# lt3042.net
KiCad netlist of a schematic drawn in EAGLE
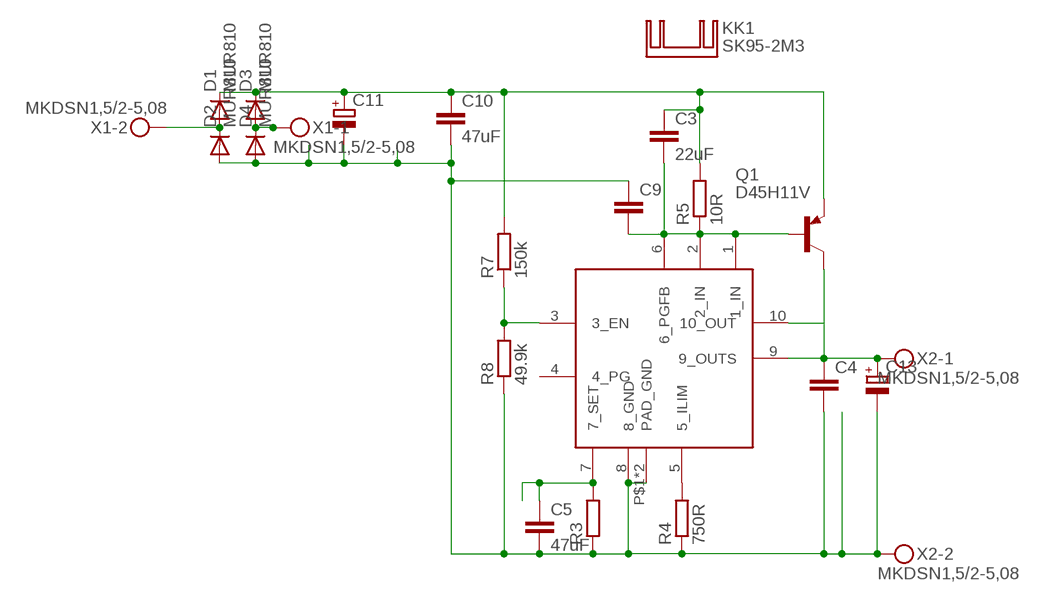
[diagram p0: schematic, sheet 1]

(export (version "E")
  (design (tool "Eeschema 10.0.6"))
  (components
    (comp (ref "C3")
      (value "22uF")
      (footprint "eagle-import:C1210")
      (libsource (lib "eagle-import") (part "C-EUC1210"))
    )
    (comp (ref "C4")
      (value "C-EUC1206")
      (footprint "eagle-import:C1206")
      (libsource (lib "eagle-import") (part "C-EUC1206"))
    )
    (comp (ref "C5")
      (value "47uF")
      (footprint "eagle-import:C1210")
      (libsource (lib "eagle-import") (part "C-EUC1210"))
    )
    (comp (ref "C9")
      (value "C-EUC1206")
      (footprint "eagle-import:C1206")
      (libsource (lib "eagle-import") (part "C-EUC1206"))
    )
    (comp (ref "C10")
      (value "47uF")
      (footprint "eagle-import:C1210")
      (libsource (lib "eagle-import") (part "C-EUC1210"))
    )
    (comp (ref "C11")
      (value "CPOL-EUE7.5-18")
      (footprint "eagle-import:E7,5-18")
      (libsource (lib "eagle-import") (part "CPOL-EUE7.5-18"))
    )
    (comp (ref "C13")
      (value "CPOL-EUE5-10.5")
      (footprint "eagle-import:E5-10,5")
      (libsource (lib "eagle-import") (part "CPOL-EUE5-10.5"))
    )
    (comp (ref "D1")
      (value "MUR810")
      (footprint "eagle-import:TO220ACS")
      (libsource (lib "eagle-import") (part "MUR810"))
    )
    (comp (ref "D2")
      (value "MUR810")
      (footprint "eagle-import:TO220ACS")
      (libsource (lib "eagle-import") (part "MUR810"))
    )
    (comp (ref "D3")
      (value "MUR810")
      (footprint "eagle-import:TO220ACS")
      (libsource (lib "eagle-import") (part "MUR810"))
    )
    (comp (ref "D4")
      (value "MUR810")
      (footprint "eagle-import:TO220ACS")
      (libsource (lib "eagle-import") (part "MUR810"))
    )
    (comp (ref "KK1")
      (value "SK95-2M3")
      (footprint "eagle-import:SK95-2M3")
      (libsource (lib "eagle-import") (part "SK95-2M3"))
    )
    (comp (ref "Q1")
      (value "D45H11V")
      (footprint "eagle-import:TO220V")
      (libsource (lib "eagle-import") (part "D45H11V"))
    )
    (comp (ref "R3")
      (value "R-EU_R1206")
      (footprint "eagle-import:R1206")
      (libsource (lib "eagle-import") (part "R-EU_R1206"))
    )
    (comp (ref "R4")
      (value "750R")
      (footprint "eagle-import:R1206")
      (libsource (lib "eagle-import") (part "R-EU_R1206"))
    )
    (comp (ref "R5")
      (value "10R")
      (footprint "eagle-import:R1206")
      (libsource (lib "eagle-import") (part "R-EU_R1206"))
    )
    (comp (ref "R7")
      (value "150k")
      (footprint "eagle-import:R1206")
      (libsource (lib "eagle-import") (part "R-EU_R1206"))
    )
    (comp (ref "R8")
      (value "49.9k")
      (footprint "eagle-import:R1206")
      (libsource (lib "eagle-import") (part "R-EU_R1206"))
    )
    (comp (ref "U$1")
      (value "LT3042")
      (footprint "eagle-import:MSOP-10")
      (libsource (lib "eagle-import") (part "LT3042"))
    )
    (comp (ref "X1")
      (value "MKDSN1,5/2-5,08")
      (footprint "eagle-import:MKDSN1,5_2-5,08")
      (libsource (lib "eagle-import") (part "MKDSN1,5/2-5,08"))
    )
    (comp (ref "X2")
      (value "MKDSN1,5/2-5,08")
      (footprint "eagle-import:MKDSN1,5_2-5,08")
      (libsource (lib "eagle-import") (part "MKDSN1,5/2-5,08"))
    )
  )
  (nets
    (net (code "1") (name "Net-(Q1-B)") (class "Default")
      (node (ref "C3") (pin "2") (pinfunction "2_2") (pintype "passive"))
      (node (ref "C9") (pin "2") (pinfunction "2_2") (pintype "passive"))
      (node (ref "Q1") (pin "1") (pinfunction "B_1") (pintype "passive"))
      (node (ref "R5") (pin "1") (pinfunction "1_1") (pintype "passive"))
      (node (ref "U$1") (pin "1") (pinfunction "1_IN_1") (pintype "bidirectional"))
      (node (ref "U$1") (pin "2") (pinfunction "2_IN_2") (pintype "bidirectional"))
      (node (ref "U$1") (pin "6") (pinfunction "6_PGFB_6") (pintype "bidirectional"))
    )
    (net (code "2") (name "Net-(Q1-C)") (class "Default")
      (node (ref "C13") (pin "+") (pinfunction "+_+") (pintype "passive"))
      (node (ref "C4") (pin "1") (pinfunction "1_1") (pintype "passive"))
      (node (ref "Q1") (pin "2") (pinfunction "C_2") (pintype "passive"))
      (node (ref "U$1") (pin "10") (pinfunction "10_OUT_10") (pintype "bidirectional"))
      (node (ref "U$1") (pin "9") (pinfunction "9_OUTS_9") (pintype "bidirectional"))
      (node (ref "X2") (pin "1") (pinfunction "KL_1") (pintype "passive"))
    )
    (net (code "3") (name "Net-(Q1-E)") (class "Default")
      (node (ref "C10") (pin "1") (pinfunction "1_1") (pintype "passive"))
      (node (ref "C11") (pin "+") (pinfunction "+_+") (pintype "passive"))
      (node (ref "C3") (pin "1") (pinfunction "1_1") (pintype "passive"))
      (node (ref "D1") (pin "C") (pinfunction "C_C") (pintype "passive"))
      (node (ref "D3") (pin "C") (pinfunction "C_C") (pintype "passive"))
      (node (ref "Q1") (pin "3") (pinfunction "E_3") (pintype "passive"))
      (node (ref "R5") (pin "2") (pinfunction "2_2") (pintype "passive"))
      (node (ref "R7") (pin "2") (pinfunction "2_2") (pintype "passive"))
    )
    (net (code "4") (name "Net-(U$1-3_EN)") (class "Default")
      (node (ref "R7") (pin "1") (pinfunction "1_1") (pintype "passive"))
      (node (ref "R8") (pin "2") (pinfunction "2_2") (pintype "passive"))
      (node (ref "U$1") (pin "3") (pinfunction "3_EN_3") (pintype "bidirectional"))
    )
    (net (code "5") (name "Net-(U$1-5_ILIM)") (class "Default")
      (node (ref "R4") (pin "2") (pinfunction "2_2") (pintype "passive"))
      (node (ref "U$1") (pin "5") (pinfunction "5_ILIM_5") (pintype "bidirectional"))
    )
    (net (code "6") (name "Net-(U$1-7_SET)") (class "Default")
      (node (ref "C5") (pin "1") (pinfunction "1_1") (pintype "passive"))
      (node (ref "R3") (pin "2") (pinfunction "2_2") (pintype "passive"))
      (node (ref "U$1") (pin "7") (pinfunction "7_SET_7") (pintype "bidirectional"))
    )
    (net (code "7") (name "Net-(U$1-8_GND)") (class "Default")
      (node (ref "C10") (pin "2") (pinfunction "2_2") (pintype "passive"))
      (node (ref "C11") (pin "-") (pinfunction "-_-") (pintype "passive"))
      (node (ref "C13") (pin "-") (pinfunction "-_-") (pintype "passive"))
      (node (ref "C4") (pin "2") (pinfunction "2_2") (pintype "passive"))
      (node (ref "C5") (pin "2") (pinfunction "2_2") (pintype "passive"))
      (node (ref "C9") (pin "1") (pinfunction "1_1") (pintype "passive"))
      (node (ref "D2") (pin "A") (pinfunction "A_A") (pintype "passive"))
      (node (ref "D4") (pin "A") (pinfunction "A_A") (pintype "passive"))
      (node (ref "R3") (pin "1") (pinfunction "1_1") (pintype "passive"))
      (node (ref "R4") (pin "1") (pinfunction "1_1") (pintype "passive"))
      (node (ref "R8") (pin "1") (pinfunction "1_1") (pintype "passive"))
      (node (ref "U$1") (pin "8") (pinfunction "8_GND_8") (pintype "bidirectional"))
      (node (ref "U$1") (pin "P$1") (pinfunction "PAD_GND_P$1") (pintype "bidirectional"))
      (node (ref "U$1") (pin "P$2") (pinfunction "PAD_GND_P$2") (pintype "bidirectional"))
      (node (ref "X2") (pin "2") (pinfunction "KL_2") (pintype "passive"))
    )
    (net (code "8") (name "Net-(X1A-KL)") (class "Default")
      (node (ref "D3") (pin "A") (pinfunction "A_A") (pintype "passive"))
      (node (ref "D4") (pin "C") (pinfunction "C_C") (pintype "passive"))
      (node (ref "X1") (pin "1") (pinfunction "KL_1") (pintype "passive"))
    )
    (net (code "9") (name "Net-(X1B-KL)") (class "Default")
      (node (ref "D1") (pin "A") (pinfunction "A_A") (pintype "passive"))
      (node (ref "D2") (pin "C") (pinfunction "C_C") (pintype "passive"))
      (node (ref "X1") (pin "2") (pinfunction "KL_2") (pintype "passive"))
    )
    (net (code "10") (name "unconnected-(U$1-4_PG-Pad4)") (class "Default")
      (node (ref "U$1") (pin "4") (pinfunction "4_PG_4") (pintype "bidirectional"))
    )
  )
)
